# 1_6.net
KiCad netlist of a schematic drawn in EAGLE
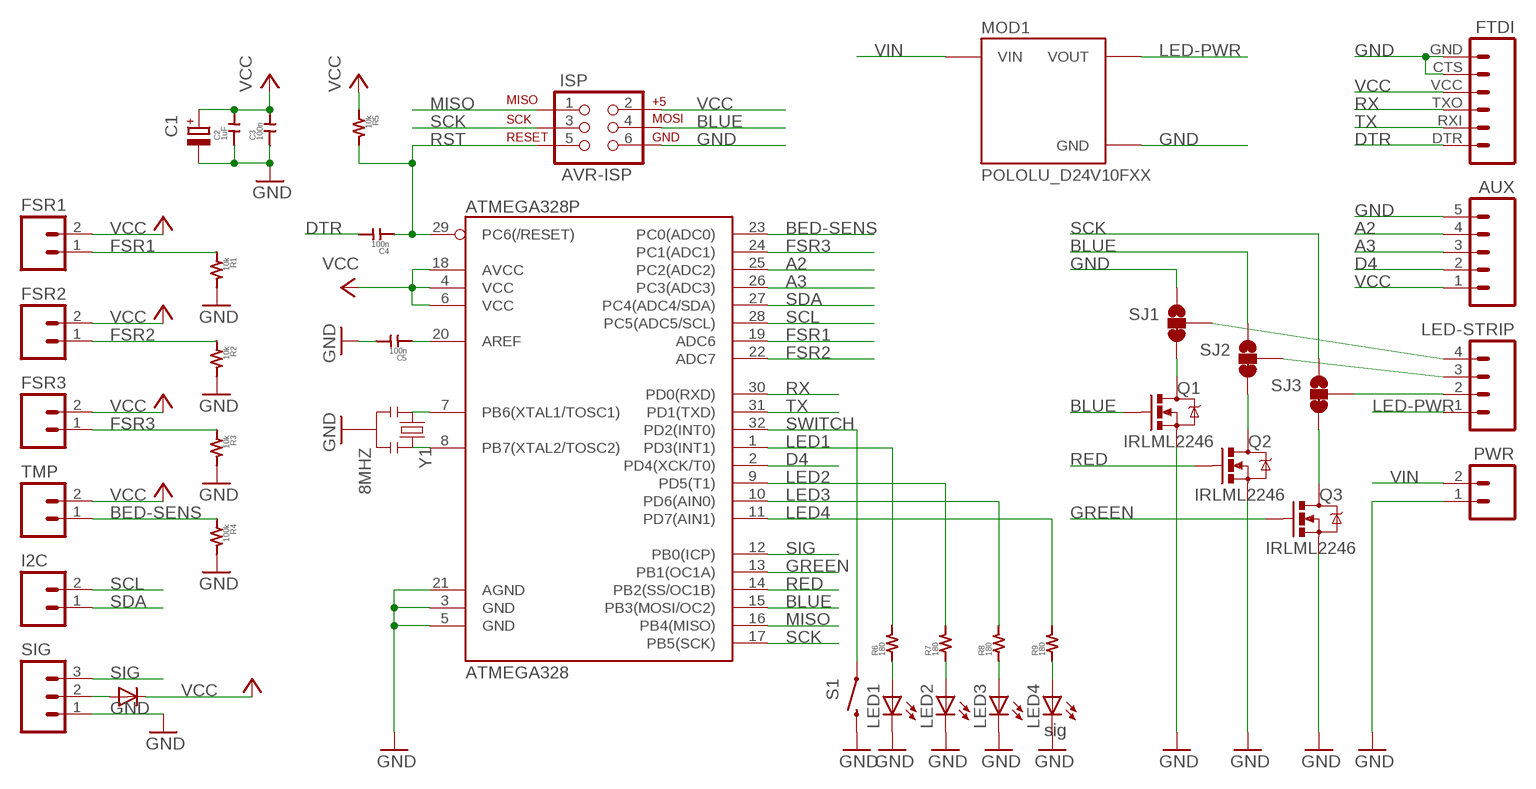
[diagram p0: schematic, sheet 1]

(export (version "E")
  (design (tool "Eeschema 10.0.6"))
  (components
    (comp (ref "ATMEGA328")
      (value "ATMEGA328P")
      (footprint "eagle-import:TQFP32-08")
      (libsource (lib "eagle-import") (part "ATMEGA328_SMT"))
    )
    (comp (ref "AUX")
      (value "M05PTH")
      (footprint "eagle-import:1X05")
      (libsource (lib "eagle-import") (part "M05PTH"))
    )
    (comp (ref "C1")
      (value "CPOL-EUSMCB")
      (footprint "eagle-import:SMC_B")
      (libsource (lib "eagle-import") (part "CPOL-EUSMCB"))
    )
    (comp (ref "C2")
      (value "1uF")
      (footprint "eagle-import:0603")
      (libsource (lib "eagle-import") (part "CAP0603"))
    )
    (comp (ref "C3")
      (value "100n")
      (footprint "eagle-import:0603")
      (libsource (lib "eagle-import") (part "CAP0603"))
    )
    (comp (ref "C4")
      (value "100n")
      (footprint "eagle-import:0603")
      (libsource (lib "eagle-import") (part "CAP0603"))
    )
    (comp (ref "C5")
      (value "100n")
      (footprint "eagle-import:0603")
      (libsource (lib "eagle-import") (part "CAP0603"))
    )
    (comp (ref "D1")
      (value "MBR0520LT")
      (footprint "eagle-import:SOD123")
      (libsource (lib "eagle-import") (part "MBR0520LT"))
    )
    (comp (ref "FSR1")
      (value "M02PTH")
      (footprint "eagle-import:1X02")
      (libsource (lib "eagle-import") (part "M02PTH"))
    )
    (comp (ref "FSR2")
      (value "M02PTH")
      (footprint "eagle-import:1X02")
      (libsource (lib "eagle-import") (part "M02PTH"))
    )
    (comp (ref "FSR3")
      (value "M02PTH")
      (footprint "eagle-import:1X02")
      (libsource (lib "eagle-import") (part "M02PTH"))
    )
    (comp (ref "FTDI")
      (value "FTDI_BASICPTH")
      (footprint "eagle-import:FTDI_BASIC")
      (libsource (lib "eagle-import") (part "FTDI_BASICPTH"))
    )
    (comp (ref "I2C")
      (value "M02PTH")
      (footprint "eagle-import:1X02")
      (libsource (lib "eagle-import") (part "M02PTH"))
    )
    (comp (ref "ISP")
      (value "AVR-ISP")
      (footprint "eagle-import:2X3_LOCK")
      (libsource (lib "eagle-import") (part "AVR_SPI_PRG_62X3_LOCK"))
    )
    (comp (ref "LED-STRIP")
      (value "M04PTH")
      (footprint "eagle-import:1X04")
      (libsource (lib "eagle-import") (part "M04PTH"))
    )
    (comp (ref "LED1")
      (value "LED3MM")
      (footprint "eagle-import:LED3MM")
      (libsource (lib "eagle-import") (part "LED3MM"))
    )
    (comp (ref "LED2")
      (value "LED3MM")
      (footprint "eagle-import:LED3MM")
      (libsource (lib "eagle-import") (part "LED3MM"))
    )
    (comp (ref "LED3")
      (value "LED3MM")
      (footprint "eagle-import:LED3MM")
      (libsource (lib "eagle-import") (part "LED3MM"))
    )
    (comp (ref "LED4")
      (value "sig")
      (footprint "eagle-import:LED3MM")
      (libsource (lib "eagle-import") (part "LED3MM"))
    )
    (comp (ref "MOD1")
      (value "POLOLU_D24V10FXX")
      (footprint "eagle-import:POLOLU_D24V10FXX_3PIN")
      (libsource (lib "eagle-import") (part "POLOLU_D24V10FXX"))
    )
    (comp (ref "PWR")
      (value "M02PTH")
      (footprint "eagle-import:1X02")
      (libsource (lib "eagle-import") (part "M02PTH"))
    )
    (comp (ref "Q1")
      (value "IRLML2246")
      (footprint "eagle-import:SOT23")
      (libsource (lib "eagle-import") (part "MOSFET-NCHANNELBSS138"))
    )
    (comp (ref "Q2")
      (value "IRLML2246")
      (footprint "eagle-import:SOT23")
      (libsource (lib "eagle-import") (part "MOSFET-NCHANNELBSS138"))
    )
    (comp (ref "Q3")
      (value "IRLML2246")
      (footprint "eagle-import:SOT23")
      (libsource (lib "eagle-import") (part "MOSFET-NCHANNELBSS138"))
    )
    (comp (ref "R1")
      (value "10k")
      (footprint "eagle-import:0603")
      (libsource (lib "eagle-import") (part "RES0603"))
    )
    (comp (ref "R2")
      (value "10k")
      (footprint "eagle-import:0603")
      (libsource (lib "eagle-import") (part "RES0603"))
    )
    (comp (ref "R3")
      (value "10k")
      (footprint "eagle-import:0603")
      (libsource (lib "eagle-import") (part "RES0603"))
    )
    (comp (ref "R4")
      (value "100k")
      (footprint "eagle-import:0603")
      (libsource (lib "eagle-import") (part "RES0603"))
    )
    (comp (ref "R5")
      (value "10k")
      (footprint "eagle-import:0603")
      (libsource (lib "eagle-import") (part "RES0603"))
    )
    (comp (ref "R6")
      (value "180")
      (footprint "eagle-import:0603")
      (libsource (lib "eagle-import") (part "RES0603"))
    )
    (comp (ref "R7")
      (value "180")
      (footprint "eagle-import:0603")
      (libsource (lib "eagle-import") (part "RES0603"))
    )
    (comp (ref "R8")
      (value "180")
      (footprint "eagle-import:0603")
      (libsource (lib "eagle-import") (part "RES0603"))
    )
    (comp (ref "R9")
      (value "180")
      (footprint "eagle-import:0603")
      (libsource (lib "eagle-import") (part "RES0603"))
    )
    (comp (ref "S1")
      (value "SWITCH-MOMENTARY-2SMD")
      (footprint "eagle-import:TACTILE_SWITCH_SMD")
      (libsource (lib "eagle-import") (part "SWITCH-MOMENTARY-2SMD"))
    )
    (comp (ref "SIG")
      (value "M03PTH")
      (footprint "eagle-import:1X03")
      (libsource (lib "eagle-import") (part "M03PTH"))
    )
    (comp (ref "SJ1")
      (value "JUMPER-PAD-3-2OF3_NC_BY_TRACE")
      (footprint "eagle-import:PAD-JUMPER-3-2OF3_NC_BY_TRACE_YES_SILK_FULL_BOX")
      (libsource (lib "eagle-import") (part "JUMPER-PAD-3-2OF3_NC_BY_TRACE"))
    )
    (comp (ref "SJ2")
      (value "JUMPER-PAD-3-2OF3_NC_BY_TRACE")
      (footprint "eagle-import:PAD-JUMPER-3-2OF3_NC_BY_TRACE_YES_SILK_FULL_BOX")
      (libsource (lib "eagle-import") (part "JUMPER-PAD-3-2OF3_NC_BY_TRACE"))
    )
    (comp (ref "SJ3")
      (value "JUMPER-PAD-3-2OF3_NC_BY_TRACE")
      (footprint "eagle-import:PAD-JUMPER-3-2OF3_NC_BY_TRACE_YES_SILK_FULL_BOX")
      (libsource (lib "eagle-import") (part "JUMPER-PAD-3-2OF3_NC_BY_TRACE"))
    )
    (comp (ref "TMP")
      (value "M02PTH")
      (footprint "eagle-import:1X02")
      (libsource (lib "eagle-import") (part "M02PTH"))
    )
    (comp (ref "Y1")
      (value "8MHZ")
      (footprint "eagle-import:RESONATOR-SMD")
      (libsource (lib "eagle-import") (part "RESONATOR8MHZ"))
    )
  )
  (nets
    (net (code "1") (name "/A2") (class "Default")
      (node (ref "ATMEGA328") (pin "25") (pinfunction "PC2(ADC2)_25") (pintype "bidirectional"))
      (node (ref "AUX") (pin "4") (pinfunction "4_4") (pintype "passive"))
    )
    (net (code "2") (name "/A3") (class "Default")
      (node (ref "ATMEGA328") (pin "26") (pinfunction "PC3(ADC3)_26") (pintype "bidirectional"))
      (node (ref "AUX") (pin "3") (pinfunction "3_3") (pintype "passive"))
    )
    (net (code "3") (name "/BED-SENS") (class "Default")
      (node (ref "ATMEGA328") (pin "23") (pinfunction "PC0(ADC0)_23") (pintype "bidirectional"))
      (node (ref "R4") (pin "1") (pinfunction "P$1_1") (pintype "bidirectional"))
      (node (ref "TMP") (pin "1") (pinfunction "1_1") (pintype "passive"))
    )
    (net (code "4") (name "/BLUE") (class "Default")
      (node (ref "ATMEGA328") (pin "15") (pinfunction "PB3(MOSI/OC2)_15") (pintype "bidirectional"))
      (node (ref "ISP") (pin "4") (pinfunction "4_4") (pintype "passive"))
      (node (ref "Q1") (pin "1") (pinfunction "G_1") (pintype "passive"))
      (node (ref "SJ2") (pin "1") (pinfunction "1_1") (pintype "passive"))
    )
    (net (code "5") (name "/D4") (class "Default")
      (node (ref "ATMEGA328") (pin "2") (pinfunction "PD4(XCK/T0)_2") (pintype "bidirectional"))
      (node (ref "AUX") (pin "2") (pinfunction "2_2") (pintype "passive"))
    )
    (net (code "6") (name "/DTR") (class "Default")
      (node (ref "C4") (pin "2") (pinfunction "P$2_2") (pintype "bidirectional"))
      (node (ref "FTDI") (pin "DTR") (pinfunction "1_DTR") (pintype "passive"))
    )
    (net (code "7") (name "/FSR1") (class "Default")
      (node (ref "ATMEGA328") (pin "19") (pinfunction "ADC6_19") (pintype "bidirectional"))
      (node (ref "FSR1") (pin "1") (pinfunction "1_1") (pintype "passive"))
      (node (ref "R1") (pin "1") (pinfunction "P$1_1") (pintype "bidirectional"))
    )
    (net (code "8") (name "/FSR2") (class "Default")
      (node (ref "ATMEGA328") (pin "22") (pinfunction "ADC7_22") (pintype "bidirectional"))
      (node (ref "FSR2") (pin "1") (pinfunction "1_1") (pintype "passive"))
      (node (ref "R2") (pin "1") (pinfunction "P$1_1") (pintype "bidirectional"))
    )
    (net (code "9") (name "/FSR3") (class "Default")
      (node (ref "ATMEGA328") (pin "24") (pinfunction "PC1(ADC1)_24") (pintype "bidirectional"))
      (node (ref "FSR3") (pin "1") (pinfunction "1_1") (pintype "passive"))
      (node (ref "R3") (pin "1") (pinfunction "P$1_1") (pintype "bidirectional"))
    )
    (net (code "10") (name "/GREEN") (class "Default")
      (node (ref "ATMEGA328") (pin "13") (pinfunction "PB1(OC1A)_13") (pintype "bidirectional"))
      (node (ref "Q3") (pin "1") (pinfunction "G_1") (pintype "passive"))
    )
    (net (code "11") (name "/LED-PWR") (class "Default")
      (node (ref "LED-STRIP") (pin "1") (pinfunction "1_1") (pintype "passive"))
      (node (ref "MOD1") (pin "VOUT") (pinfunction "VOUT_VOUT") (pintype "output"))
    )
    (net (code "12") (name "/LED1") (class "Default")
      (node (ref "ATMEGA328") (pin "1") (pinfunction "PD3(INT1)_1") (pintype "bidirectional"))
      (node (ref "R6") (pin "2") (pinfunction "P$2_2") (pintype "bidirectional"))
    )
    (net (code "13") (name "/LED2") (class "Default")
      (node (ref "ATMEGA328") (pin "9") (pinfunction "PD5(T1)_9") (pintype "bidirectional"))
      (node (ref "R7") (pin "2") (pinfunction "P$2_2") (pintype "bidirectional"))
    )
    (net (code "14") (name "/LED3") (class "Default")
      (node (ref "ATMEGA328") (pin "10") (pinfunction "PD6(AIN0)_10") (pintype "bidirectional"))
      (node (ref "R8") (pin "2") (pinfunction "P$2_2") (pintype "bidirectional"))
    )
    (net (code "15") (name "/LED4") (class "Default")
      (node (ref "ATMEGA328") (pin "11") (pinfunction "PD7(AIN1)_11") (pintype "bidirectional"))
      (node (ref "R9") (pin "2") (pinfunction "P$2_2") (pintype "bidirectional"))
    )
    (net (code "16") (name "/MISO") (class "Default")
      (node (ref "ATMEGA328") (pin "16") (pinfunction "PB4(MISO)_16") (pintype "bidirectional"))
      (node (ref "ISP") (pin "1") (pinfunction "1_1") (pintype "passive"))
    )
    (net (code "17") (name "/RED") (class "Default")
      (node (ref "ATMEGA328") (pin "14") (pinfunction "PB2(SS/OC1B)_14") (pintype "bidirectional"))
      (node (ref "Q2") (pin "1") (pinfunction "G_1") (pintype "passive"))
    )
    (net (code "18") (name "/RST") (class "Default")
      (node (ref "ATMEGA328") (pin "29") (pinfunction "PC6(/RESET)_29") (pintype "bidirectional"))
      (node (ref "C4") (pin "1") (pinfunction "P$1_1") (pintype "bidirectional"))
      (node (ref "ISP") (pin "5") (pinfunction "5_5") (pintype "passive"))
      (node (ref "R5") (pin "2") (pinfunction "P$2_2") (pintype "bidirectional"))
    )
    (net (code "19") (name "/RX") (class "Default")
      (node (ref "ATMEGA328") (pin "30") (pinfunction "PD0(RXD)_30") (pintype "bidirectional"))
      (node (ref "FTDI") (pin "TXO") (pinfunction "3_TXO") (pintype "passive"))
    )
    (net (code "20") (name "/SCK") (class "Default")
      (node (ref "ATMEGA328") (pin "17") (pinfunction "PB5(SCK)_17") (pintype "bidirectional"))
      (node (ref "ISP") (pin "3") (pinfunction "3_3") (pintype "passive"))
      (node (ref "SJ3") (pin "1") (pinfunction "1_1") (pintype "passive"))
    )
    (net (code "21") (name "/SCL") (class "Default")
      (node (ref "ATMEGA328") (pin "28") (pinfunction "PC5(ADC5/SCL)_28") (pintype "bidirectional"))
      (node (ref "I2C") (pin "2") (pinfunction "2_2") (pintype "passive"))
    )
    (net (code "22") (name "/SDA") (class "Default")
      (node (ref "ATMEGA328") (pin "27") (pinfunction "PC4(ADC4/SDA)_27") (pintype "bidirectional"))
      (node (ref "I2C") (pin "1") (pinfunction "1_1") (pintype "passive"))
    )
    (net (code "23") (name "/SIG") (class "Default")
      (node (ref "ATMEGA328") (pin "12") (pinfunction "PB0(ICP)_12") (pintype "bidirectional"))
      (node (ref "SIG") (pin "3") (pinfunction "3_3") (pintype "passive"))
    )
    (net (code "24") (name "/SWITCH") (class "Default")
      (node (ref "ATMEGA328") (pin "32") (pinfunction "PD2(INT0)_32") (pintype "bidirectional"))
      (node (ref "S1") (pin "1") (pinfunction "1_1") (pintype "passive"))
      (node (ref "S1") (pin "2") (pinfunction "1_2") (pintype "passive"))
    )
    (net (code "25") (name "/TX") (class "Default")
      (node (ref "ATMEGA328") (pin "31") (pinfunction "PD1(TXD)_31") (pintype "bidirectional"))
      (node (ref "FTDI") (pin "RXI") (pinfunction "2_RXI") (pintype "passive"))
    )
    (net (code "26") (name "/VIN") (class "Default")
      (node (ref "MOD1") (pin "VIN") (pinfunction "VIN_VIN") (pintype "power_in"))
      (node (ref "PWR") (pin "2") (pinfunction "2_2") (pintype "passive"))
    )
    (net (code "27") (name "GND") (class "Default")
      (node (ref "ATMEGA328") (pin "21") (pinfunction "AGND_21") (pintype "bidirectional"))
      (node (ref "ATMEGA328") (pin "3") (pinfunction "GND_3") (pintype "bidirectional"))
      (node (ref "ATMEGA328") (pin "5") (pinfunction "GND_5") (pintype "bidirectional"))
      (node (ref "AUX") (pin "5") (pinfunction "5_5") (pintype "passive"))
      (node (ref "C1") (pin "-") (pinfunction "-_-") (pintype "passive"))
      (node (ref "C2") (pin "1") (pinfunction "P$1_1") (pintype "bidirectional"))
      (node (ref "C3") (pin "1") (pinfunction "P$1_1") (pintype "bidirectional"))
      (node (ref "C5") (pin "2") (pinfunction "P$2_2") (pintype "bidirectional"))
      (node (ref "FTDI") (pin "CTS") (pinfunction "5_CTS") (pintype "passive"))
      (node (ref "FTDI") (pin "GND") (pinfunction "6_GND") (pintype "passive"))
      (node (ref "ISP") (pin "6") (pinfunction "6_6") (pintype "passive"))
      (node (ref "LED1") (pin "K") (pinfunction "C_K") (pintype "passive"))
      (node (ref "LED2") (pin "K") (pinfunction "C_K") (pintype "passive"))
      (node (ref "LED3") (pin "K") (pinfunction "C_K") (pintype "passive"))
      (node (ref "LED4") (pin "K") (pinfunction "C_K") (pintype "passive"))
      (node (ref "MOD1") (pin "GND") (pinfunction "GND_GND") (pintype "power_in"))
      (node (ref "PWR") (pin "1") (pinfunction "1_1") (pintype "passive"))
      (node (ref "Q1") (pin "2") (pinfunction "S_2") (pintype "passive"))
      (node (ref "Q2") (pin "2") (pinfunction "S_2") (pintype "passive"))
      (node (ref "Q3") (pin "2") (pinfunction "S_2") (pintype "passive"))
      (node (ref "R1") (pin "2") (pinfunction "P$2_2") (pintype "bidirectional"))
      (node (ref "R2") (pin "2") (pinfunction "P$2_2") (pintype "bidirectional"))
      (node (ref "R3") (pin "2") (pinfunction "P$2_2") (pintype "bidirectional"))
      (node (ref "R4") (pin "2") (pinfunction "P$2_2") (pintype "bidirectional"))
      (node (ref "S1") (pin "3") (pinfunction "2_3") (pintype "passive"))
      (node (ref "S1") (pin "4") (pinfunction "2_4") (pintype "passive"))
      (node (ref "SIG") (pin "1") (pinfunction "1_1") (pintype "passive"))
      (node (ref "SJ1") (pin "1") (pinfunction "1_1") (pintype "passive"))
      (node (ref "Y1") (pin "2") (pinfunction "2_2") (pintype "passive"))
    )
    (net (code "28") (name "Net-(ATMEGA328-AREF)") (class "Default")
      (node (ref "ATMEGA328") (pin "20") (pinfunction "AREF_20") (pintype "bidirectional"))
      (node (ref "C5") (pin "1") (pinfunction "P$1_1") (pintype "bidirectional"))
    )
    (net (code "29") (name "Net-(ATMEGA328-PB6(XTAL1{slash}TOSC1))") (class "Default")
      (node (ref "ATMEGA328") (pin "7") (pinfunction "PB6(XTAL1/TOSC1)_7") (pintype "bidirectional"))
      (node (ref "Y1") (pin "1") (pinfunction "1_1") (pintype "passive"))
    )
    (net (code "30") (name "Net-(ATMEGA328-PB7(XTAL2{slash}TOSC2))") (class "Default")
      (node (ref "ATMEGA328") (pin "8") (pinfunction "PB7(XTAL2/TOSC2)_8") (pintype "bidirectional"))
      (node (ref "Y1") (pin "3") (pinfunction "3_3") (pintype "passive"))
    )
    (net (code "31") (name "Net-(D1-PadA)") (class "Default")
      (node (ref "D1") (pin "A") (pinfunction "A_A") (pintype "passive"))
      (node (ref "SIG") (pin "2") (pinfunction "2_2") (pintype "passive"))
    )
    (net (code "32") (name "Net-(LED-STRIP-Pad2)") (class "Default")
      (node (ref "LED-STRIP") (pin "2") (pinfunction "2_2") (pintype "passive"))
      (node (ref "SJ3") (pin "2") (pinfunction "2_2") (pintype "passive"))
    )
    (net (code "33") (name "Net-(LED-STRIP-Pad3)") (class "Default")
      (node (ref "LED-STRIP") (pin "3") (pinfunction "3_3") (pintype "passive"))
      (node (ref "SJ2") (pin "2") (pinfunction "2_2") (pintype "passive"))
    )
    (net (code "34") (name "Net-(LED-STRIP-Pad4)") (class "Default")
      (node (ref "LED-STRIP") (pin "4") (pinfunction "4_4") (pintype "passive"))
      (node (ref "SJ1") (pin "2") (pinfunction "2_2") (pintype "passive"))
    )
    (net (code "35") (name "Net-(Q1-D)") (class "Default")
      (node (ref "Q1") (pin "3") (pinfunction "D_3") (pintype "passive"))
      (node (ref "SJ1") (pin "3") (pinfunction "3_3") (pintype "passive"))
    )
    (net (code "36") (name "Net-(Q2-D)") (class "Default")
      (node (ref "Q2") (pin "3") (pinfunction "D_3") (pintype "passive"))
      (node (ref "SJ2") (pin "3") (pinfunction "3_3") (pintype "passive"))
    )
    (net (code "37") (name "Net-(Q3-D)") (class "Default")
      (node (ref "Q3") (pin "3") (pinfunction "D_3") (pintype "passive"))
      (node (ref "SJ3") (pin "3") (pinfunction "3_3") (pintype "passive"))
    )
    (net (code "38") (name "Net-(R6-P$1)") (class "Default")
      (node (ref "LED1") (pin "A") (pinfunction "A_A") (pintype "passive"))
      (node (ref "R6") (pin "1") (pinfunction "P$1_1") (pintype "bidirectional"))
    )
    (net (code "39") (name "Net-(R7-P$1)") (class "Default")
      (node (ref "LED2") (pin "A") (pinfunction "A_A") (pintype "passive"))
      (node (ref "R7") (pin "1") (pinfunction "P$1_1") (pintype "bidirectional"))
    )
    (net (code "40") (name "Net-(R8-P$1)") (class "Default")
      (node (ref "LED3") (pin "A") (pinfunction "A_A") (pintype "passive"))
      (node (ref "R8") (pin "1") (pinfunction "P$1_1") (pintype "bidirectional"))
    )
    (net (code "41") (name "Net-(R9-P$1)") (class "Default")
      (node (ref "LED4") (pin "A") (pinfunction "A_A") (pintype "passive"))
      (node (ref "R9") (pin "1") (pinfunction "P$1_1") (pintype "bidirectional"))
    )
    (net (code "42") (name "VCC") (class "Default")
      (node (ref "ATMEGA328") (pin "18") (pinfunction "AVCC_18") (pintype "bidirectional"))
      (node (ref "ATMEGA328") (pin "4") (pinfunction "VCC_4") (pintype "bidirectional"))
      (node (ref "ATMEGA328") (pin "6") (pinfunction "VCC_6") (pintype "bidirectional"))
      (node (ref "AUX") (pin "1") (pinfunction "1_1") (pintype "passive"))
      (node (ref "C1") (pin "+") (pinfunction "+_+") (pintype "passive"))
      (node (ref "C2") (pin "2") (pinfunction "P$2_2") (pintype "bidirectional"))
      (node (ref "C3") (pin "2") (pinfunction "P$2_2") (pintype "bidirectional"))
      (node (ref "D1") (pin "C") (pinfunction "C_C") (pintype "passive"))
      (node (ref "FSR1") (pin "2") (pinfunction "2_2") (pintype "passive"))
      (node (ref "FSR2") (pin "2") (pinfunction "2_2") (pintype "passive"))
      (node (ref "FSR3") (pin "2") (pinfunction "2_2") (pintype "passive"))
      (node (ref "FTDI") (pin "VCC") (pinfunction "4_VCC") (pintype "passive"))
      (node (ref "ISP") (pin "2") (pinfunction "2_2") (pintype "passive"))
      (node (ref "R5") (pin "1") (pinfunction "P$1_1") (pintype "bidirectional"))
      (node (ref "TMP") (pin "2") (pinfunction "2_2") (pintype "passive"))
    )
  )
)
